# ADC.net
KiCad netlist of a schematic drawn in Altium Designer
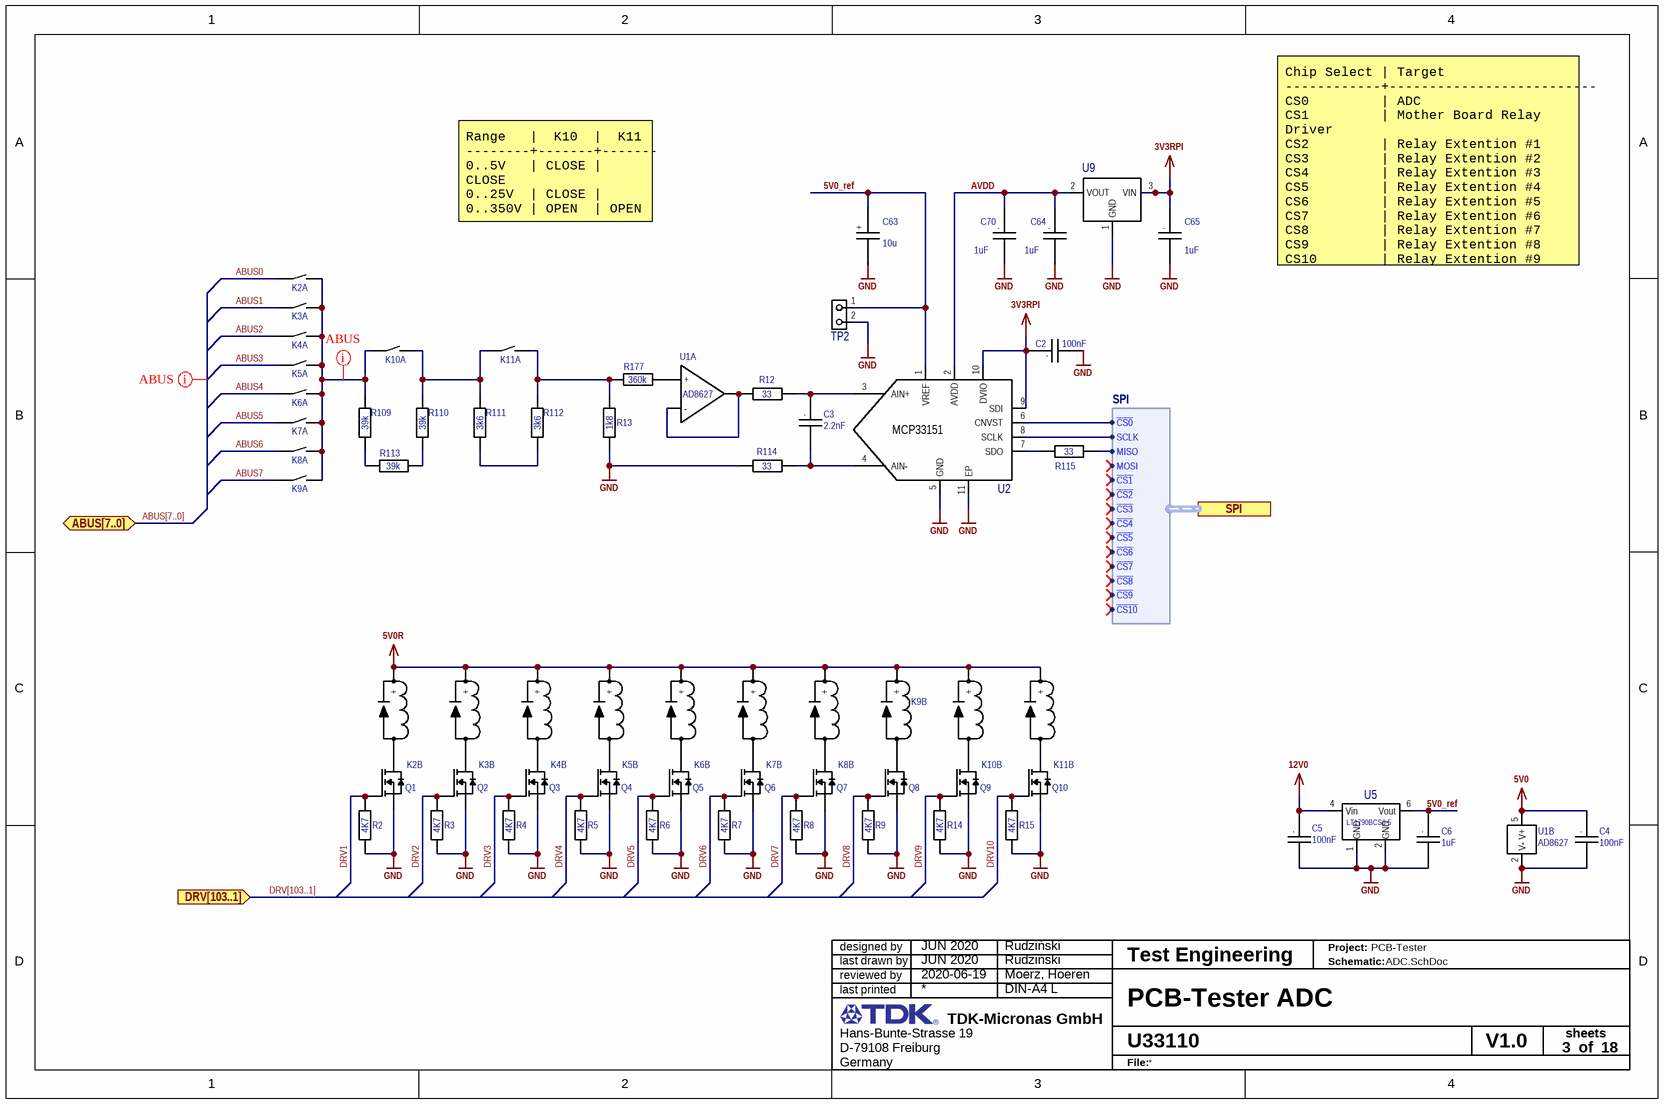
[diagram p0: ADC.SchDoc]

(export (version "E")
  (design (tool "Eeschema 10.0.6"))
  (components
    (comp (ref "C2")
      (value "100nF")
      (footprint "C0402 Reflow")
      (description "CAP CER 0.1UF 25V X7R 0402")
      (fields
        (field (name "TOLERANCE") "±5%")
        (field (name "02. DISTRIBUTOR PART NUMBER") "311-2077-6-ND")
        (field (name "13. CREATED DATE/NAME") "AUG2018/Hören")
      )
      (libsource (lib "chickenfood") (part "C"))
    )
    (comp (ref "C3")
      (value "2.2nF")
      (footprint "C0603 Reflow")
      (description "CAP CER 2200PF 50V X7R 0402")
      (fields
        (field (name "TOLERANCE") "±5%")
        (field (name "02. DISTRIBUTOR PART NUMBER") "1276-1532-6-ND")
        (field (name "13. CREATED DATE/NAME") "AUG2018/Hören")
      )
      (libsource (lib "chickenfood") (part "C"))
    )
    (comp (ref "C4")
      (value "100nF")
      (footprint "C0402 Reflow")
      (description "CAP CER 0.1UF 25V X7R 0402")
      (fields
        (field (name "TOLERANCE") "±5%")
        (field (name "02. DISTRIBUTOR PART NUMBER") "311-2077-6-ND")
        (field (name "13. CREATED DATE/NAME") "AUG2018/Hören")
      )
      (libsource (lib "chickenfood") (part "C"))
    )
    (comp (ref "C5")
      (value "100nF")
      (footprint "C0402 Reflow")
      (description "CAP CER 0.1UF 25V X7R 0402")
      (fields
        (field (name "TOLERANCE") "±5%")
        (field (name "02. DISTRIBUTOR PART NUMBER") "311-2077-6-ND")
        (field (name "13. CREATED DATE/NAME") "AUG2018/Hören")
      )
      (libsource (lib "chickenfood") (part "C"))
    )
    (comp (ref "C6")
      (value "1uF")
      (footprint "C0402 Reflow")
      (description "CAP CER 1UF 6.3V X7R 0402")
      (fields
        (field (name "TOLERANCE") "±10%")
        (field (name "02. DISTRIBUTOR PART NUMBER") "490-13339-6-ND")
        (field (name "13. CREATED DATE/NAME") "AUG2018/Hören")
      )
      (libsource (lib "chickenfood") (part "C"))
    )
    (comp (ref "C63")
      (value "10u")
      (footprint "CAP_TAN_B")
      (description "CAP TANT 10UF 20% 16V 1411")
      (fields
        (field (name "02. DISTRIBUTOR PART NUMBER") "718-2344-1-ND")
        (field (name "07. MANUFACTURER  PART NUMBER") "TMCHB1C106MTRF")
      )
      (libsource (lib "PCB-Tester-Board-V1") (part "C+_TAN"))
    )
    (comp (ref "C64")
      (value "1uF")
      (footprint "C0402 Reflow")
      (description "CAP CER 1UF 6.3V X7R 0402")
      (fields
        (field (name "TOLERANCE") "±10%")
        (field (name "02. DISTRIBUTOR PART NUMBER") "490-13339-6-ND")
        (field (name "13. CREATED DATE/NAME") "AUG2018/Hören")
      )
      (libsource (lib "chickenfood") (part "C"))
    )
    (comp (ref "C65")
      (value "1uF")
      (footprint "C0402 Reflow")
      (description "CAP CER 1UF 6.3V X7R 0402")
      (fields
        (field (name "TOLERANCE") "±10%")
        (field (name "02. DISTRIBUTOR PART NUMBER") "490-13339-6-ND")
        (field (name "13. CREATED DATE/NAME") "AUG2018/Hören")
      )
      (libsource (lib "chickenfood") (part "C"))
    )
    (comp (ref "C70")
      (value "1uF")
      (footprint "C0402 Reflow")
      (description "CAP CER 1UF 6.3V X7R 0402")
      (fields
        (field (name "TOLERANCE") "±10%")
        (field (name "02. DISTRIBUTOR PART NUMBER") "490-13339-6-ND")
        (field (name "13. CREATED DATE/NAME") "AUG2018/Hören")
      )
      (libsource (lib "chickenfood") (part "C"))
    )
    (comp (ref "K2")
      (value "K")
      (footprint "118-1A")
      (description "5V Signal Relais, Normal Open")
      (fields
        (field (name "02. DISTRIBUTOR PART NUMBER") "118-1-A-5/2D")
        (field (name "13. CREATED DATE/NAME") "20.12.17 S. Kaiser")
      )
      (libsource (lib "chickenfood") (part "118-1-A-5/2D"))
    )
    (comp (ref "K3")
      (value "K")
      (footprint "118-1A")
      (description "5V Signal Relais, Normal Open")
      (fields
        (field (name "02. DISTRIBUTOR PART NUMBER") "118-1-A-5/2D")
        (field (name "13. CREATED DATE/NAME") "20.12.17 S. Kaiser")
      )
      (libsource (lib "chickenfood") (part "118-1-A-5/2D"))
    )
    (comp (ref "K4")
      (value "K")
      (footprint "118-1A")
      (description "5V Signal Relais, Normal Open")
      (fields
        (field (name "02. DISTRIBUTOR PART NUMBER") "118-1-A-5/2D")
        (field (name "13. CREATED DATE/NAME") "20.12.17 S. Kaiser")
      )
      (libsource (lib "") (part "118-1-A-5/2D_1"))
    )
    (comp (ref "K5")
      (value "K")
      (footprint "118-1A")
      (description "5V Signal Relais, Normal Open")
      (fields
        (field (name "02. DISTRIBUTOR PART NUMBER") "118-1-A-5/2D")
        (field (name "13. CREATED DATE/NAME") "20.12.17 S. Kaiser")
      )
      (libsource (lib "chickenfood") (part "118-1-A-5/2D"))
    )
    (comp (ref "K6")
      (value "K")
      (footprint "118-1A")
      (description "5V Signal Relais, Normal Open")
      (fields
        (field (name "02. DISTRIBUTOR PART NUMBER") "118-1-A-5/2D")
        (field (name "13. CREATED DATE/NAME") "20.12.17 S. Kaiser")
      )
      (libsource (lib "chickenfood") (part "118-1-A-5/2D"))
    )
    (comp (ref "K7")
      (value "K")
      (footprint "118-1A")
      (description "5V Signal Relais, Normal Open")
      (fields
        (field (name "02. DISTRIBUTOR PART NUMBER") "118-1-A-5/2D")
        (field (name "13. CREATED DATE/NAME") "20.12.17 S. Kaiser")
      )
      (libsource (lib "chickenfood") (part "118-1-A-5/2D"))
    )
    (comp (ref "K8")
      (value "K")
      (footprint "118-1A")
      (description "5V Signal Relais, Normal Open")
      (fields
        (field (name "02. DISTRIBUTOR PART NUMBER") "118-1-A-5/2D")
        (field (name "13. CREATED DATE/NAME") "20.12.17 S. Kaiser")
      )
      (libsource (lib "") (part "118-1-A-5/2D_1"))
    )
    (comp (ref "K9")
      (value "K")
      (footprint "118-1A")
      (description "5V Signal Relais, Normal Open")
      (fields
        (field (name "02. DISTRIBUTOR PART NUMBER") "118-1-A-5/2D")
        (field (name "13. CREATED DATE/NAME") "20.12.17 S. Kaiser")
      )
      (libsource (lib "") (part "118-1-A-5/2D_1"))
    )
    (comp (ref "K10")
      (value "K")
      (footprint "118-1A")
      (description "5V Signal Relais, Normal Open")
      (fields
        (field (name "02. DISTRIBUTOR PART NUMBER") "118-1-A-5/2D")
        (field (name "13. CREATED DATE/NAME") "20.12.17 S. Kaiser")
      )
      (libsource (lib "") (part "118-1-A-5/2D_1"))
    )
    (comp (ref "K11")
      (value "K")
      (footprint "118-1A")
      (description "5V Signal Relais, Normal Open")
      (fields
        (field (name "02. DISTRIBUTOR PART NUMBER") "118-1-A-5/2D")
        (field (name "13. CREATED DATE/NAME") "20.12.17 S. Kaiser")
      )
      (libsource (lib "chickenfood") (part "118-1-A-5/2D"))
    )
    (comp (ref "Q1")
      (value "Q")
      (footprint "SOT23-3")
      (description "MOSFET N-CH 25V 680MA SOT-23")
      (fields
        (field (name "02. DISTRIBUTOR PART NUMBER") "FDV303NDKR-ND")
        (field (name "07. MANUFACTURER  PART NUMBER") "FDV303N")
        (field (name "13. CREATED DATE/NAME") "AUG 2018 / Hören")
      )
      (libsource (lib "SCT8-Board1") (part "FDV303N"))
    )
    (comp (ref "Q2")
      (value "Q")
      (footprint "SOT23-3")
      (description "MOSFET N-CH 25V 680MA SOT-23")
      (fields
        (field (name "02. DISTRIBUTOR PART NUMBER") "FDV303NDKR-ND")
        (field (name "07. MANUFACTURER  PART NUMBER") "FDV303N")
        (field (name "13. CREATED DATE/NAME") "AUG 2018 / Hören")
      )
      (libsource (lib "SCT8-Board1") (part "FDV303N"))
    )
    (comp (ref "Q3")
      (value "Q")
      (footprint "SOT23-3")
      (description "MOSFET N-CH 25V 680MA SOT-23")
      (fields
        (field (name "02. DISTRIBUTOR PART NUMBER") "FDV303NDKR-ND")
        (field (name "07. MANUFACTURER  PART NUMBER") "FDV303N")
        (field (name "13. CREATED DATE/NAME") "AUG 2018 / Hören")
      )
      (libsource (lib "SCT8-Board1") (part "FDV303N"))
    )
    (comp (ref "Q4")
      (value "Q")
      (footprint "SOT23-3")
      (description "MOSFET N-CH 25V 680MA SOT-23")
      (fields
        (field (name "02. DISTRIBUTOR PART NUMBER") "FDV303NDKR-ND")
        (field (name "07. MANUFACTURER  PART NUMBER") "FDV303N")
        (field (name "13. CREATED DATE/NAME") "AUG 2018 / Hören")
      )
      (libsource (lib "SCT8-Board1") (part "FDV303N"))
    )
    (comp (ref "Q5")
      (value "Q")
      (footprint "SOT23-3")
      (description "MOSFET N-CH 25V 680MA SOT-23")
      (fields
        (field (name "02. DISTRIBUTOR PART NUMBER") "FDV303NDKR-ND")
        (field (name "07. MANUFACTURER  PART NUMBER") "FDV303N")
        (field (name "13. CREATED DATE/NAME") "AUG 2018 / Hören")
      )
      (libsource (lib "SCT8-Board1") (part "FDV303N"))
    )
    (comp (ref "Q6")
      (value "Q")
      (footprint "SOT23-3")
      (description "MOSFET N-CH 25V 680MA SOT-23")
      (fields
        (field (name "02. DISTRIBUTOR PART NUMBER") "FDV303NDKR-ND")
        (field (name "07. MANUFACTURER  PART NUMBER") "FDV303N")
        (field (name "13. CREATED DATE/NAME") "AUG 2018 / Hören")
      )
      (libsource (lib "SCT8-Board1") (part "FDV303N"))
    )
    (comp (ref "Q7")
      (value "Q")
      (footprint "SOT23-3")
      (description "MOSFET N-CH 25V 680MA SOT-23")
      (fields
        (field (name "02. DISTRIBUTOR PART NUMBER") "FDV303NDKR-ND")
        (field (name "07. MANUFACTURER  PART NUMBER") "FDV303N")
        (field (name "13. CREATED DATE/NAME") "AUG 2018 / Hören")
      )
      (libsource (lib "SCT8-Board1") (part "FDV303N"))
    )
    (comp (ref "Q8")
      (value "Q")
      (footprint "SOT23-3")
      (description "MOSFET N-CH 25V 680MA SOT-23")
      (fields
        (field (name "02. DISTRIBUTOR PART NUMBER") "FDV303NDKR-ND")
        (field (name "07. MANUFACTURER  PART NUMBER") "FDV303N")
        (field (name "13. CREATED DATE/NAME") "AUG 2018 / Hören")
      )
      (libsource (lib "SCT8-Board1") (part "FDV303N"))
    )
    (comp (ref "Q9")
      (value "Q")
      (footprint "SOT23-3")
      (description "MOSFET N-CH 25V 680MA SOT-23")
      (fields
        (field (name "02. DISTRIBUTOR PART NUMBER") "FDV303NDKR-ND")
        (field (name "07. MANUFACTURER  PART NUMBER") "FDV303N")
        (field (name "13. CREATED DATE/NAME") "AUG 2018 / Hören")
      )
      (libsource (lib "SCT8-Board1") (part "FDV303N"))
    )
    (comp (ref "Q10")
      (value "Q")
      (footprint "SOT23-3")
      (description "MOSFET N-CH 25V 680MA SOT-23")
      (fields
        (field (name "02. DISTRIBUTOR PART NUMBER") "FDV303NDKR-ND")
        (field (name "07. MANUFACTURER  PART NUMBER") "FDV303N")
        (field (name "13. CREATED DATE/NAME") "AUG 2018 / Hören")
      )
      (libsource (lib "SCT8-Board1") (part "FDV303N"))
    )
    (comp (ref "R2")
      (value "4K7")
      (footprint "R0603 Reflow")
      (description "RES SMD 4.7K OHM 1% 1/10W 0603")
      (fields
        (field (name "TOLERANCE") "±1%")
        (field (name "02. DISTRIBUTOR PART NUMBER") "311-4.70KHRCT-ND")
        (field (name "13. CREATED DATE/NAME") "AUG2018/Hören")
      )
      (libsource (lib "chickenfood") (part "R"))
    )
    (comp (ref "R3")
      (value "4K7")
      (footprint "R0603 Reflow")
      (description "RES SMD 4.7K OHM 1% 1/10W 0603")
      (fields
        (field (name "TOLERANCE") "±1%")
        (field (name "02. DISTRIBUTOR PART NUMBER") "311-4.70KHRCT-ND")
        (field (name "13. CREATED DATE/NAME") "AUG2018/Hören")
      )
      (libsource (lib "chickenfood") (part "R"))
    )
    (comp (ref "R4")
      (value "4K7")
      (footprint "R0603 Reflow")
      (description "RES SMD 4.7K OHM 1% 1/10W 0603")
      (fields
        (field (name "TOLERANCE") "±1%")
        (field (name "02. DISTRIBUTOR PART NUMBER") "311-4.70KHRCT-ND")
        (field (name "13. CREATED DATE/NAME") "AUG2018/Hören")
      )
      (libsource (lib "chickenfood") (part "R"))
    )
    (comp (ref "R5")
      (value "4K7")
      (footprint "R0603 Reflow")
      (description "RES SMD 4.7K OHM 1% 1/10W 0603")
      (fields
        (field (name "TOLERANCE") "±1%")
        (field (name "02. DISTRIBUTOR PART NUMBER") "311-4.70KHRCT-ND")
        (field (name "13. CREATED DATE/NAME") "AUG2018/Hören")
      )
      (libsource (lib "chickenfood") (part "R"))
    )
    (comp (ref "R6")
      (value "4K7")
      (footprint "R0603 Reflow")
      (description "RES SMD 4.7K OHM 1% 1/10W 0603")
      (fields
        (field (name "TOLERANCE") "±1%")
        (field (name "02. DISTRIBUTOR PART NUMBER") "311-4.70KHRCT-ND")
        (field (name "13. CREATED DATE/NAME") "AUG2018/Hören")
      )
      (libsource (lib "chickenfood") (part "R"))
    )
    (comp (ref "R7")
      (value "4K7")
      (footprint "R0603 Reflow")
      (description "RES SMD 4.7K OHM 1% 1/10W 0603")
      (fields
        (field (name "TOLERANCE") "±1%")
        (field (name "02. DISTRIBUTOR PART NUMBER") "311-4.70KHRCT-ND")
        (field (name "13. CREATED DATE/NAME") "AUG2018/Hören")
      )
      (libsource (lib "chickenfood") (part "R"))
    )
    (comp (ref "R8")
      (value "4K7")
      (footprint "R0603 Reflow")
      (description "RES SMD 4.7K OHM 1% 1/10W 0603")
      (fields
        (field (name "TOLERANCE") "±1%")
        (field (name "02. DISTRIBUTOR PART NUMBER") "311-4.70KHRCT-ND")
        (field (name "13. CREATED DATE/NAME") "AUG2018/Hören")
      )
      (libsource (lib "chickenfood") (part "R"))
    )
    (comp (ref "R9")
      (value "4K7")
      (footprint "R0603 Reflow")
      (description "RES SMD 4.7K OHM 1% 1/10W 0603")
      (fields
        (field (name "TOLERANCE") "±1%")
        (field (name "02. DISTRIBUTOR PART NUMBER") "311-4.70KHRCT-ND")
        (field (name "13. CREATED DATE/NAME") "AUG2018/Hören")
      )
      (libsource (lib "chickenfood") (part "R"))
    )
    (comp (ref "R12")
      (value "33")
      (footprint "R0402 Reflow")
      (description "RES SMD 33 OHM 1% 1/16W 0402")
      (fields
        (field (name "TOLERANCE") "±1%")
        (field (name "02. DISTRIBUTOR PART NUMBER") "311-33.0LRDKR-ND")
        (field (name "13. CREATED DATE/NAME") "AUG2018/Hören")
      )
      (libsource (lib "") (part "R_1"))
    )
    (comp (ref "R13")
      (value "1k8")
      (footprint "R0603 Reflow")
      (description "RES SMD 1.8K OHM 1% 1/16W 0402")
      (fields
        (field (name "TOLERANCE") "±1%")
        (field (name "02. DISTRIBUTOR PART NUMBER") "311-1.80KLRCT-ND")
        (field (name "13. CREATED DATE/NAME") "AUG2018/Hören")
      )
      (libsource (lib "chickenfood") (part "R"))
    )
    (comp (ref "R14")
      (value "4K7")
      (footprint "R0603 Reflow")
      (description "RES SMD 4.7K OHM 1% 1/10W 0603")
      (fields
        (field (name "TOLERANCE") "±1%")
        (field (name "02. DISTRIBUTOR PART NUMBER") "311-4.70KHRCT-ND")
        (field (name "13. CREATED DATE/NAME") "AUG2018/Hören")
      )
      (libsource (lib "chickenfood") (part "R"))
    )
    (comp (ref "R15")
      (value "4K7")
      (footprint "R0603 Reflow")
      (description "RES SMD 4.7K OHM 1% 1/10W 0603")
      (fields
        (field (name "TOLERANCE") "±1%")
        (field (name "02. DISTRIBUTOR PART NUMBER") "311-4.70KHRCT-ND")
        (field (name "13. CREATED DATE/NAME") "AUG2018/Hören")
      )
      (libsource (lib "chickenfood") (part "R"))
    )
    (comp (ref "R109")
      (value "39k")
      (footprint "R2512 Reflow")
      (description "CRGP 2512 39K 1%")
      (fields
        (field (name "TOLERANCE") "±1%")
        (field (name "02. DISTRIBUTOR PART NUMBER") "A130740CT-ND")
        (field (name "13. CREATED DATE/NAME") "AUG2018/Hören")
      )
      (libsource (lib "PCB-Tester-Board-V1") (part "R"))
    )
    (comp (ref "R110")
      (value "39k")
      (footprint "R2512 Reflow")
      (description "CRGP 2512 39K 1%")
      (fields
        (field (name "TOLERANCE") "±1%")
        (field (name "02. DISTRIBUTOR PART NUMBER") "A130740CT-ND")
        (field (name "13. CREATED DATE/NAME") "AUG2018/Hören")
      )
      (libsource (lib "PCB-Tester-Board-V1") (part "R"))
    )
    (comp (ref "R111")
      (value "3k6")
      (footprint "R0603 Reflow")
      (description "RES SMD 3.6K OHM 1% 1/10W 0603")
      (fields
        (field (name "TOLERANCE") "±1%")
        (field (name "02. DISTRIBUTOR PART NUMBER") "311-3.60KHRCT-ND")
        (field (name "13. CREATED DATE/NAME") "AUG2018/Hören")
      )
      (libsource (lib "PCB-Tester-Board-V1") (part "R"))
    )
    (comp (ref "R112")
      (value "3k6")
      (footprint "R0603 Reflow")
      (description "RES SMD 3.6K OHM 1% 1/10W 0603")
      (fields
        (field (name "TOLERANCE") "±1%")
        (field (name "02. DISTRIBUTOR PART NUMBER") "311-3.60KHRCT-ND")
        (field (name "13. CREATED DATE/NAME") "AUG2018/Hören")
      )
      (libsource (lib "PCB-Tester-Board-V1") (part "R"))
    )
    (comp (ref "R113")
      (value "39k")
      (footprint "R2512 Reflow")
      (description "CRGP 2512 39K 1%")
      (fields
        (field (name "TOLERANCE") "±1%")
        (field (name "02. DISTRIBUTOR PART NUMBER") "A130740CT-ND")
        (field (name "13. CREATED DATE/NAME") "AUG2018/Hören")
      )
      (libsource (lib "") (part "R_1"))
    )
    (comp (ref "R114")
      (value "33")
      (footprint "R0402 Reflow")
      (description "RES SMD 33 OHM 1% 1/16W 0402")
      (fields
        (field (name "TOLERANCE") "±1%")
        (field (name "02. DISTRIBUTOR PART NUMBER") "311-33.0LRDKR-ND")
        (field (name "13. CREATED DATE/NAME") "AUG2018/Hören")
      )
      (libsource (lib "") (part "R_1"))
    )
    (comp (ref "R115")
      (value "33")
      (footprint "R0402 Reflow")
      (description "RES SMD 33 OHM 1% 1/16W 0402")
      (fields
        (field (name "TOLERANCE") "±1%")
        (field (name "02. DISTRIBUTOR PART NUMBER") "311-33.0LRDKR-ND")
        (field (name "13. CREATED DATE/NAME") "AUG2018/Hören")
      )
      (libsource (lib "PCB-Tester-Board-V1") (part "R_19"))
    )
    (comp (ref "R177")
      (value "360k")
      (footprint "R1206 Reflow")
      (description "RES SMD 360K OHM 1% 1/4W 1206")
      (fields
        (field (name "TOLERANCE") "±1%")
        (field (name "02. DISTRIBUTOR PART NUMBER") "311-360KFRCT-ND")
        (field (name "13. CREATED DATE/NAME") "AUG2018/Hören")
      )
      (libsource (lib "") (part "R_1"))
    )
    (comp (ref "TP2")
      (value "TP")
      (footprint "DualTestpoint 100mils")
      (description "Dual testpoint, pitch 2.54mm")
      (fields
        (field (name "02. DISTRIBUTOR PART NUMBER") "HMTSW-103-07-G-S-240")
        (field (name "13. CREATED DATE/NAME") "AUG2018/Hören")
      )
      (libsource (lib "PCB-Tester-Board-V1") (part "DualTestpoint 100mils"))
    )
    (comp (ref "U1")
      (value "U")
      (footprint "tom:SC70-5")
      (description "IC OPAMP JFET 5MHZ RRO SC70-5")
      (fields
        (field (name "02. DISTRIBUTOR PART NUMBER") "AD8627AKSZ-R2DKR-ND")
        (field (name "07. MANUFACTURER  PART NUMBER") "AD8627AKSZ-R2")
        (field (name "PART") "AD8627")
        (field (name "13. CREATED DATE/NAME") "AUG 2018 / Hören")
      )
      (libsource (lib "tom") (part "AD8627"))
    )
    (comp (ref "U2")
      (value "U")
      (footprint "TDFN10EP")
      (description "14-BIT 1 MSPS SGL CH SGL-ENDED S")
      (fields
        (field (name "02. DISTRIBUTOR PART NUMBER") "MCP33151-10T-E/MNDKR-ND")
        (field (name "07. MANUFACTURER  PART NUMBER") "MCP33151-10T-E/MN")
        (field (name "NICNAME") "MCP33151")
        (field (name "13. CREATED DATE/NAME") "AUG 2018 / Hören")
      )
      (libsource (lib "tom") (part "MCP33151-10T-E/MN"))
    )
    (comp (ref "U5")
      (value "U")
      (footprint "TSOT23-6(S6)")
      (description "IC VREF SERIES 5V, 0.1% TSOT-23-6")
      (fields
        (field (name "02. DISTRIBUTOR PART NUMBER") "LT1790BCS6-5#TRMPBFDKR-ND")
        (field (name "07. MANUFACTURER  PART NUMBER") "LT1790BCS6-5#TRMPBF")
        (field (name "NICNAME") "LT1790BCS6-5")
        (field (name "13. CREATED DATE/NAME") "AUG 2018 / Hören")
      )
      (libsource (lib "tom") (part "LT1790BCS6-5"))
    )
    (comp (ref "U9")
      (value "U")
      (footprint "SOT23-3")
      (description "IC REG LINEAR 1.8V 250MA SOT23-3")
      (fields
        (field (name "02. DISTRIBUTOR PART NUMBER") "AP2138N-1.8TRG1DICT-ND")
        (field (name "07. MANUFACTURER  PART NUMBER") "AP2138N-1.8TRG1")
      )
      (libsource (lib "PCB-Tester-Board-V1") (part "AP2138N"))
    )
  )
  (nets
    (net (code "95") (name "/5V0_ref") (class "Default")
      (node (ref "C6") (pin "1") (pinfunction "1_1") (pintype "passive"))
      (node (ref "C63") (pin "1") (pinfunction "1_1") (pintype "passive"))
      (node (ref "TP2") (pin "1") (pinfunction "1_1") (pintype "passive"))
      (node (ref "U2") (pin "1") (pinfunction "VREF_1") (pintype "passive"))
      (node (ref "U5") (pin "6") (pinfunction "Vout_6") (pintype "passive"))
    )
    (net (code "96") (name "/ABUS0") (class "Default")
      (node (ref "K2") (pin "4") (pinfunction "CB_4") (pintype "passive"))
    )
    (net (code "97") (name "/ABUS1") (class "Default")
      (node (ref "K3") (pin "4") (pinfunction "CB_4") (pintype "passive"))
    )
    (net (code "98") (name "/ABUS2") (class "Default")
      (node (ref "K4") (pin "4") (pinfunction "CB_4") (pintype "passive"))
    )
    (net (code "99") (name "/ABUS3") (class "Default")
      (node (ref "K5") (pin "4") (pinfunction "CB_4") (pintype "passive"))
    )
    (net (code "100") (name "/ABUS4") (class "Default")
      (node (ref "K6") (pin "4") (pinfunction "CB_4") (pintype "passive"))
    )
    (net (code "101") (name "/ABUS5") (class "Default")
      (node (ref "K7") (pin "4") (pinfunction "CB_4") (pintype "passive"))
    )
    (net (code "102") (name "/ABUS6") (class "Default")
      (node (ref "K8") (pin "4") (pinfunction "CB_4") (pintype "passive"))
    )
    (net (code "103") (name "/ABUS7") (class "Default")
      (node (ref "K9") (pin "4") (pinfunction "CB_4") (pintype "passive"))
    )
    (net (code "105") (name "/AVDD") (class "Default")
      (node (ref "C64") (pin "1") (pinfunction "1_1") (pintype "passive"))
      (node (ref "C70") (pin "1") (pinfunction "1_1") (pintype "passive"))
      (node (ref "U2") (pin "2") (pinfunction "AVDD_2") (pintype "passive"))
      (node (ref "U9") (pin "2") (pinfunction "VOUT_2") (pintype "passive"))
    )
    (net (code "106") (name "/DRV1") (class "Default")
      (node (ref "Q1") (pin "1") (pinfunction "G_1") (pintype "passive"))
      (node (ref "R2") (pin "2") (pinfunction "2_2") (pintype "passive"))
    )
    (net (code "107") (name "/DRV2") (class "Default")
      (node (ref "Q2") (pin "1") (pinfunction "G_1") (pintype "passive"))
      (node (ref "R3") (pin "2") (pinfunction "2_2") (pintype "passive"))
    )
    (net (code "108") (name "/DRV3") (class "Default")
      (node (ref "Q3") (pin "1") (pinfunction "G_1") (pintype "passive"))
      (node (ref "R4") (pin "2") (pinfunction "2_2") (pintype "passive"))
    )
    (net (code "109") (name "/DRV4") (class "Default")
      (node (ref "Q4") (pin "1") (pinfunction "G_1") (pintype "passive"))
      (node (ref "R5") (pin "2") (pinfunction "2_2") (pintype "passive"))
    )
    (net (code "110") (name "/DRV5") (class "Default")
      (node (ref "Q5") (pin "1") (pinfunction "G_1") (pintype "passive"))
      (node (ref "R6") (pin "2") (pinfunction "2_2") (pintype "passive"))
    )
    (net (code "111") (name "/DRV6") (class "Default")
      (node (ref "Q6") (pin "1") (pinfunction "G_1") (pintype "passive"))
      (node (ref "R7") (pin "2") (pinfunction "2_2") (pintype "passive"))
    )
    (net (code "112") (name "/DRV7") (class "Default")
      (node (ref "Q7") (pin "1") (pinfunction "G_1") (pintype "passive"))
      (node (ref "R8") (pin "2") (pinfunction "2_2") (pintype "passive"))
    )
    (net (code "113") (name "/DRV8") (class "Default")
      (node (ref "Q8") (pin "1") (pinfunction "G_1") (pintype "passive"))
      (node (ref "R9") (pin "2") (pinfunction "2_2") (pintype "passive"))
    )
    (net (code "114") (name "/DRV9") (class "Default")
      (node (ref "Q9") (pin "1") (pinfunction "G_1") (pintype "passive"))
      (node (ref "R14") (pin "2") (pinfunction "2_2") (pintype "passive"))
    )
    (net (code "115") (name "/DRV10") (class "Default")
      (node (ref "Q10") (pin "1") (pinfunction "G_1") (pintype "passive"))
      (node (ref "R15") (pin "2") (pinfunction "2_2") (pintype "passive"))
    )
    (net (code "117") (name "/MISO") (class "Default")
      (node (ref "R115") (pin "2") (pinfunction "2_2") (pintype "passive"))
    )
    (net (code "118") (name "/SCLK") (class "Default")
      (node (ref "U2") (pin "8") (pinfunction "SCLK_8") (pintype "passive"))
    )
    (net (code "120") (name "/~{CS0}") (class "Default")
      (node (ref "U2") (pin "6") (pinfunction "CNVST_6") (pintype "passive"))
    )
    (net (code "121") (name "3V3RPI") (class "Default")
      (node (ref "C2") (pin "1") (pinfunction "1_1") (pintype "passive"))
      (node (ref "C65") (pin "1") (pinfunction "1_1") (pintype "passive"))
      (node (ref "U2") (pin "10") (pinfunction "DVIO_10") (pintype "passive"))
      (node (ref "U2") (pin "9") (pinfunction "SDI_9") (pintype "passive"))
      (node (ref "U9") (pin "3") (pinfunction "VIN_3") (pintype "passive"))
    )
    (net (code "122") (name "5V0") (class "Default")
      (node (ref "C4") (pin "1") (pinfunction "1_1") (pintype "passive"))
      (node (ref "U1") (pin "5") (pinfunction "V+_5") (pintype "passive"))
    )
    (net (code "123") (name "5V0R") (class "Default")
      (node (ref "K10") (pin "1") (pinfunction "+_1") (pintype "passive"))
      (node (ref "K11") (pin "1") (pinfunction "+_1") (pintype "passive"))
      (node (ref "K2") (pin "1") (pinfunction "+_1") (pintype "passive"))
      (node (ref "K3") (pin "1") (pinfunction "+_1") (pintype "passive"))
      (node (ref "K4") (pin "1") (pinfunction "+_1") (pintype "passive"))
      (node (ref "K5") (pin "1") (pinfunction "+_1") (pintype "passive"))
      (node (ref "K6") (pin "1") (pinfunction "+_1") (pintype "passive"))
      (node (ref "K7") (pin "1") (pinfunction "+_1") (pintype "passive"))
      (node (ref "K8") (pin "1") (pinfunction "+_1") (pintype "passive"))
      (node (ref "K9") (pin "1") (pinfunction "+_1") (pintype "passive"))
    )
    (net (code "124") (name "12V0") (class "Default")
      (node (ref "C5") (pin "1") (pinfunction "1_1") (pintype "passive"))
      (node (ref "U5") (pin "4") (pinfunction "Vin_4") (pintype "passive"))
    )
    (net (code "125") (name "GND") (class "Default")
      (node (ref "C2") (pin "2") (pinfunction "2_2") (pintype "passive"))
      (node (ref "C4") (pin "2") (pinfunction "2_2") (pintype "passive"))
      (node (ref "C5") (pin "2") (pinfunction "2_2") (pintype "passive"))
      (node (ref "C6") (pin "2") (pinfunction "2_2") (pintype "passive"))
      (node (ref "C63") (pin "2") (pinfunction "2_2") (pintype "passive"))
      (node (ref "C64") (pin "2") (pinfunction "2_2") (pintype "passive"))
      (node (ref "C65") (pin "2") (pinfunction "2_2") (pintype "passive"))
      (node (ref "C70") (pin "2") (pinfunction "2_2") (pintype "passive"))
      (node (ref "Q1") (pin "2") (pinfunction "S_2") (pintype "passive"))
      (node (ref "Q10") (pin "2") (pinfunction "S_2") (pintype "passive"))
      (node (ref "Q2") (pin "2") (pinfunction "S_2") (pintype "passive"))
      (node (ref "Q3") (pin "2") (pinfunction "S_2") (pintype "passive"))
      (node (ref "Q4") (pin "2") (pinfunction "S_2") (pintype "passive"))
      (node (ref "Q5") (pin "2") (pinfunction "S_2") (pintype "passive"))
      (node (ref "Q6") (pin "2") (pinfunction "S_2") (pintype "passive"))
      (node (ref "Q7") (pin "2") (pinfunction "S_2") (pintype "passive"))
      (node (ref "Q8") (pin "2") (pinfunction "S_2") (pintype "passive"))
      (node (ref "Q9") (pin "2") (pinfunction "S_2") (pintype "passive"))
      (node (ref "R114") (pin "2") (pinfunction "2_2") (pintype "passive"))
      (node (ref "R13") (pin "1") (pinfunction "1_1") (pintype "passive"))
      (node (ref "R14") (pin "1") (pinfunction "1_1") (pintype "passive"))
      (node (ref "R15") (pin "1") (pinfunction "1_1") (pintype "passive"))
      (node (ref "R2") (pin "1") (pinfunction "1_1") (pintype "passive"))
      (node (ref "R3") (pin "1") (pinfunction "1_1") (pintype "passive"))
      (node (ref "R4") (pin "1") (pinfunction "1_1") (pintype "passive"))
      (node (ref "R5") (pin "1") (pinfunction "1_1") (pintype "passive"))
      (node (ref "R6") (pin "1") (pinfunction "1_1") (pintype "passive"))
      (node (ref "R7") (pin "1") (pinfunction "1_1") (pintype "passive"))
      (node (ref "R8") (pin "1") (pinfunction "1_1") (pintype "passive"))
      (node (ref "R9") (pin "1") (pinfunction "1_1") (pintype "passive"))
      (node (ref "TP2") (pin "2") (pinfunction "2_2") (pintype "passive"))
      (node (ref "U1") (pin "2") (pinfunction "V-_2") (pintype "passive"))
      (node (ref "U2") (pin "11") (pinfunction "EP_11") (pintype "passive"))
      (node (ref "U2") (pin "5") (pinfunction "GND_5") (pintype "passive"))
      (node (ref "U5") (pin "1") (pinfunction "GND_1") (pintype "passive"))
      (node (ref "U5") (pin "2") (pinfunction "GND_2") (pintype "passive"))
      (node (ref "U9") (pin "1") (pinfunction "GND_1") (pintype "passive"))
    )
    (net (code "126") (name "Net-(K2B--)") (class "Default")
      (node (ref "K2") (pin "2") (pinfunction "-_2") (pintype "passive"))
      (node (ref "Q1") (pin "3") (pinfunction "D_3") (pintype "passive"))
    )
    (net (code "127") (name "Net-(K3B--)") (class "Default")
      (node (ref "K3") (pin "2") (pinfunction "-_2") (pintype "passive"))
      (node (ref "Q2") (pin "3") (pinfunction "D_3") (pintype "passive"))
    )
    (net (code "128") (name "Net-(K4B--)") (class "Default")
      (node (ref "K4") (pin "2") (pinfunction "-_2") (pintype "passive"))
      (node (ref "Q3") (pin "3") (pinfunction "D_3") (pintype "passive"))
    )
    (net (code "129") (name "Net-(K5B--)") (class "Default")
      (node (ref "K5") (pin "2") (pinfunction "-_2") (pintype "passive"))
      (node (ref "Q4") (pin "3") (pinfunction "D_3") (pintype "passive"))
    )
    (net (code "130") (name "Net-(K6B--)") (class "Default")
      (node (ref "K6") (pin "2") (pinfunction "-_2") (pintype "passive"))
      (node (ref "Q5") (pin "3") (pinfunction "D_3") (pintype "passive"))
    )
    (net (code "131") (name "Net-(K7B--)") (class "Default")
      (node (ref "K7") (pin "2") (pinfunction "-_2") (pintype "passive"))
      (node (ref "Q6") (pin "3") (pinfunction "D_3") (pintype "passive"))
    )
    (net (code "132") (name "Net-(K8B--)") (class "Default")
      (node (ref "K8") (pin "2") (pinfunction "-_2") (pintype "passive"))
      (node (ref "Q7") (pin "3") (pinfunction "D_3") (pintype "passive"))
    )
    (net (code "133") (name "Net-(K9B--)") (class "Default")
      (node (ref "K9") (pin "2") (pinfunction "-_2") (pintype "passive"))
      (node (ref "Q8") (pin "3") (pinfunction "D_3") (pintype "passive"))
    )
    (net (code "134") (name "Net-(K10A-CA)") (class "Default")
      (node (ref "K10") (pin "3") (pinfunction "CA_3") (pintype "passive"))
      (node (ref "K11") (pin "4") (pinfunction "CB_4") (pintype "passive"))
      (node (ref "R110") (pin "2") (pinfunction "2_2") (pintype "passive"))
      (node (ref "R111") (pin "2") (pinfunction "2_2") (pintype "passive"))
    )
    (net (code "135") (name "Net-(K10A-CB)") (class "Default")
      (node (ref "K10") (pin "4") (pinfunction "CB_4") (pintype "passive"))
      (node (ref "K2") (pin "3") (pinfunction "CA_3") (pintype "passive"))
      (node (ref "K3") (pin "3") (pinfunction "CA_3") (pintype "passive"))
      (node (ref "K4") (pin "3") (pinfunction "CA_3") (pintype "passive"))
      (node (ref "K5") (pin "3") (pinfunction "CA_3") (pintype "passive"))
      (node (ref "K6") (pin "3") (pinfunction "CA_3") (pintype "passive"))
      (node (ref "K7") (pin "3") (pinfunction "CA_3") (pintype "passive"))
      (node (ref "K8") (pin "3") (pinfunction "CA_3") (pintype "passive"))
      (node (ref "K9") (pin "3") (pinfunction "CA_3") (pintype "passive"))
      (node (ref "R109") (pin "2") (pinfunction "2_2") (pintype "passive"))
    )
    (net (code "136") (name "Net-(K10B--)") (class "Default")
      (node (ref "K10") (pin "2") (pinfunction "-_2") (pintype "passive"))
      (node (ref "Q9") (pin "3") (pinfunction "D_3") (pintype "passive"))
    )
    (net (code "137") (name "Net-(K11A-CA)") (class "Default")
      (node (ref "K11") (pin "3") (pinfunction "CA_3") (pintype "passive"))
      (node (ref "R112") (pin "2") (pinfunction "2_2") (pintype "passive"))
      (node (ref "R13") (pin "2") (pinfunction "2_2") (pintype "passive"))
      (node (ref "R177") (pin "2") (pinfunction "2_2") (pintype "passive"))
    )
    (net (code "138") (name "Net-(K11B--)") (class "Default")
      (node (ref "K11") (pin "2") (pinfunction "-_2") (pintype "passive"))
      (node (ref "Q10") (pin "3") (pinfunction "D_3") (pintype "passive"))
    )
    (net (code "139") (name "Net-(R109-Pad1)") (class "Default")
      (node (ref "R109") (pin "1") (pinfunction "1_1") (pintype "passive"))
      (node (ref "R113") (pin "2") (pinfunction "2_2") (pintype "passive"))
    )
    (net (code "140") (name "Net-(R110-Pad1)") (class "Default")
      (node (ref "R110") (pin "1") (pinfunction "1_1") (pintype "passive"))
      (node (ref "R113") (pin "1") (pinfunction "1_1") (pintype "passive"))
    )
    (net (code "141") (name "Net-(R111-Pad1)") (class "Default")
      (node (ref "R111") (pin "1") (pinfunction "1_1") (pintype "passive"))
      (node (ref "R112") (pin "1") (pinfunction "1_1") (pintype "passive"))
    )
    (net (code "142") (name "Net-(U1A-+)") (class "Default")
      (node (ref "R177") (pin "1") (pinfunction "1_1") (pintype "passive"))
      (node (ref "U1") (pin "3") (pinfunction "+_3") (pintype "passive"))
    )
    (net (code "143") (name "Net-(U1A--)") (class "Default")
      (node (ref "R12") (pin "2") (pinfunction "2_2") (pintype "passive"))
      (node (ref "U1") (pin "1") (pinfunction "Out_1") (pintype "passive"))
      (node (ref "U1") (pin "4") (pinfunction "-_4") (pintype "passive"))
    )
    (net (code "144") (name "Net-(U2-AIN+)") (class "Default")
      (node (ref "C3") (pin "1") (pinfunction "1_1") (pintype "passive"))
      (node (ref "R12") (pin "1") (pinfunction "1_1") (pintype "passive"))
      (node (ref "U2") (pin "3") (pinfunction "AIN+_3") (pintype "passive"))
    )
    (net (code "145") (name "Net-(U2-AIN-)") (class "Default")
      (node (ref "C3") (pin "2") (pinfunction "2_2") (pintype "passive"))
      (node (ref "R114") (pin "1") (pinfunction "1_1") (pintype "passive"))
      (node (ref "U2") (pin "4") (pinfunction "AIN-_4") (pintype "passive"))
    )
    (net (code "146") (name "Net-(U2-SDO)") (class "Default")
      (node (ref "R115") (pin "1") (pinfunction "1_1") (pintype "passive"))
      (node (ref "U2") (pin "7") (pinfunction "SDO_7") (pintype "passive"))
    )
  )
)
